# USB_Type_C.net
KiCad netlist of a schematic drawn in Altium Designer
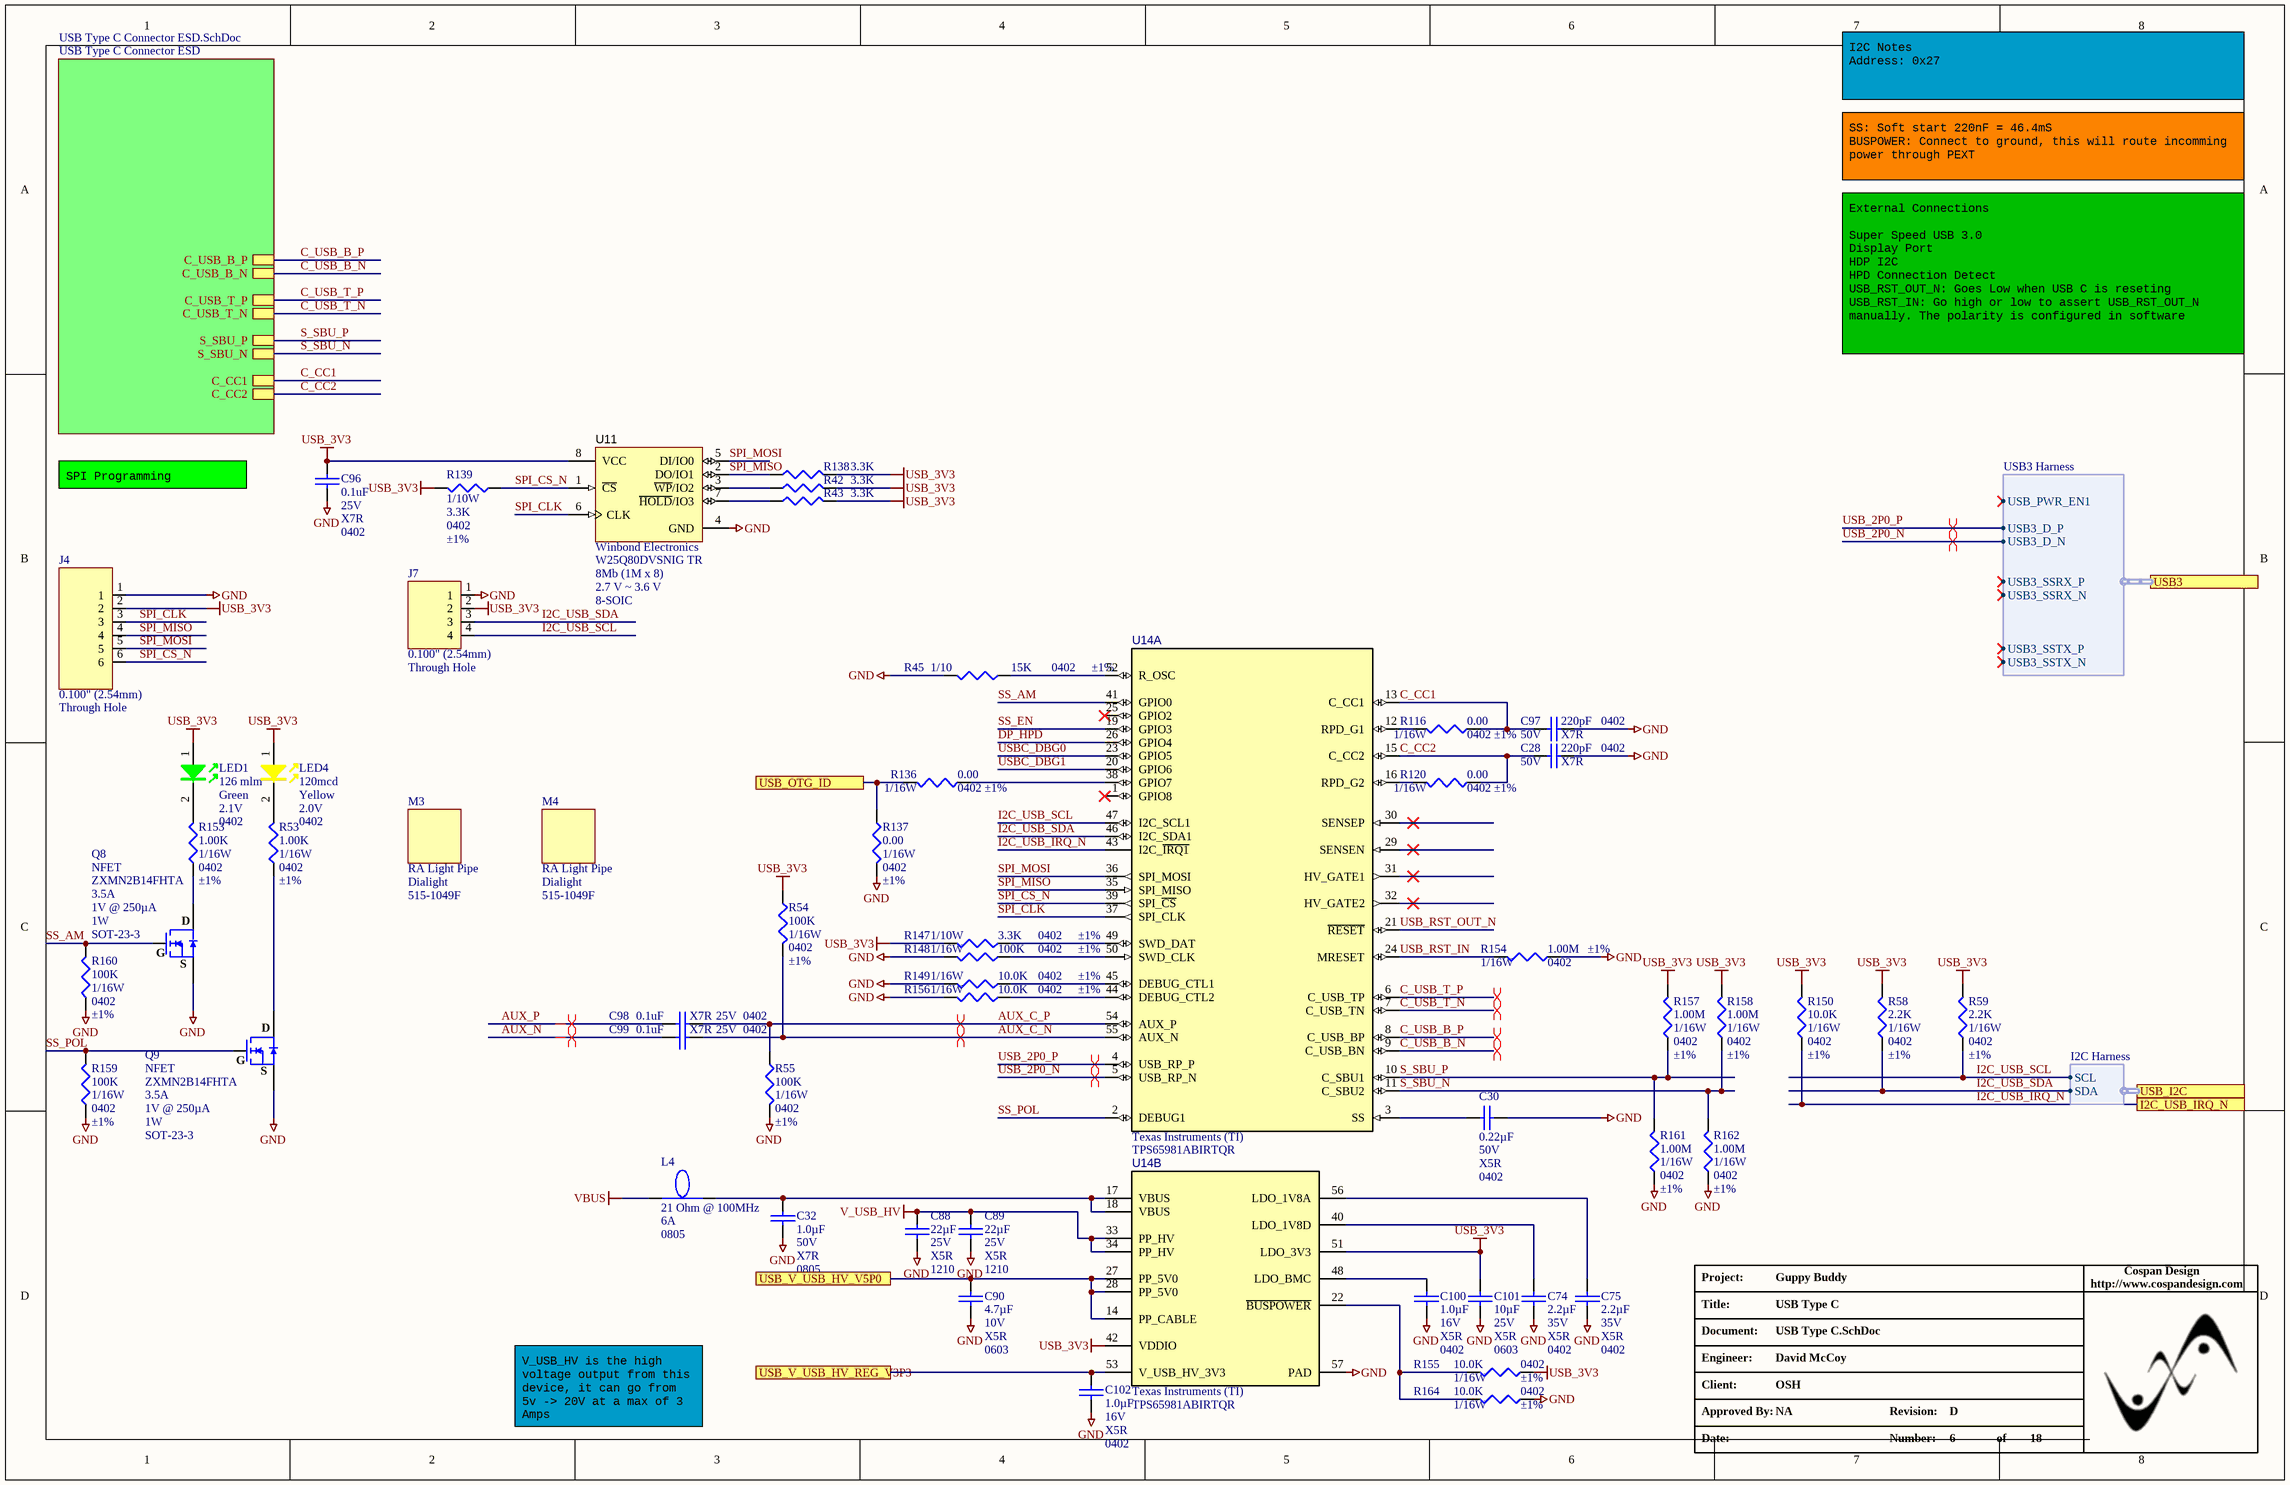
[diagram p0: USB Type C.SchDoc]

(export (version "E")
  (design (tool "Eeschema 10.0.6"))
  (components
    (comp (ref "C28")
      (value "220pF")
      (footprint "C_0402")
      (description "CAP CER 220PF 50V 10% X7R 0402")
      (fields
        (field (name "MANUFACTURER") "Murata Electronics North America")
        (field (name "MANUFACTURER PART NUMBER") "GRM155R71H221KA01D")
        (field (name "CAPACITANCE") "220pF")
        (field (name "VOLTAGE - RATED") "50V")
        (field (name "TEMPERATURE COEFFICIENT") "X7R")
        (field (name "PACKAGE / CASE") "0402")
      )
      (libsource (lib "Main Library") (part "C_0402_220PF_50V"))
    )
    (comp (ref "C30")
      (value "C_0402_0.22UF_50V")
      (footprint "C_0402")
      (description "CAP CER 0.22UF 50V X5R 0402")
      (fields
        (field (name "MANUFACTURER") "Taiyo Yuden")
        (field (name "MANUFACTURER PART NUMBER") "UMK105BJ224KV-F")
        (field (name "CAPACITANCE") "0.22µF")
        (field (name "VOLTAGE - RATED") "50V")
        (field (name "TEMPERATURE COEFFICIENT") "X5R")
        (field (name "PACKAGE / CASE") "0402")
      )
      (libsource (lib "Main Library") (part "C_0402_0.22UF_50V"))
    )
    (comp (ref "C32")
      (value "1.0uF")
      (footprint "C_ERA-0805")
      (description "CAP CER 1UF 50V X7R 0805")
      (fields
        (field (name "TOLERANCE") "10%")
        (field (name "CAPACITANCE") "1.0µF")
        (field (name "VOLTAGE - RATED") "50V")
        (field (name "TEMPERATURE COEFFICIENT") "X7R")
        (field (name "PACKAGE / CASE") "0805")
        (field (name "VOLTAGE") "50V")
      )
      (libsource (lib "Main LibraryX") (part "C_0805_1.0uF_50V"))
    )
    (comp (ref "C74")
      (value "C_0402_2.2uF_35V")
      (footprint "C_0402")
      (description "CAP CER 2.2UF 35V 20% X5R 0402")
      (fields
        (field (name "MANUFACTURER") "TDK Corporation")
        (field (name "MANUFACTURER PART NUMBER") "C1005X5R1V225K050BC")
        (field (name "CAPACITANCE") "2.2µF")
        (field (name "VOLTAGE - RATED") "35V")
        (field (name "TEMPERATURE COEFFICIENT") "X5R")
        (field (name "PACKAGE / CASE") "0402")
      )
      (libsource (lib "Main Library") (part "C_0402_2.2uF_35V"))
    )
    (comp (ref "C75")
      (value "C_0402_2.2uF_35V")
      (footprint "C_0402")
      (description "CAP CER 2.2UF 35V 20% X5R 0402")
      (fields
        (field (name "MANUFACTURER") "TDK Corporation")
        (field (name "MANUFACTURER PART NUMBER") "C1005X5R1V225K050BC")
        (field (name "CAPACITANCE") "2.2µF")
        (field (name "VOLTAGE - RATED") "35V")
        (field (name "TEMPERATURE COEFFICIENT") "X5R")
        (field (name "PACKAGE / CASE") "0402")
      )
      (libsource (lib "Main Library") (part "C_0402_2.2uF_35V"))
    )
    (comp (ref "C88")
      (value "22µF")
      (footprint "C_14-1210")
      (description "CAP CER 22UF 25V 20% X5R 1210")
      (fields
        (field (name "MANUFACTURER") "Taiyo Yuden")
        (field (name "MANUFACTURER PART NUMBER") "TMK325BJ226MM-T")
        (field (name "CAPACITANCE") "22µF")
        (field (name "VOLTAGE - RATED") "25V")
        (field (name "TEMPERATURE COEFFICIENT") "X5R")
        (field (name "PACKAGE / CASE") "1210")
      )
      (libsource (lib "Main Library") (part "C_1210_22µF"))
    )
    (comp (ref "C89")
      (value "22µF")
      (footprint "C_14-1210")
      (description "CAP CER 22UF 25V 20% X5R 1210")
      (fields
        (field (name "MANUFACTURER") "Taiyo Yuden")
        (field (name "MANUFACTURER PART NUMBER") "TMK325BJ226MM-T")
        (field (name "CAPACITANCE") "22µF")
        (field (name "VOLTAGE - RATED") "25V")
        (field (name "TEMPERATURE COEFFICIENT") "X5R")
        (field (name "PACKAGE / CASE") "1210")
      )
      (libsource (lib "Main Library") (part "C_1210_22µF"))
    )
    (comp (ref "C90")
      (value "4.7µF")
      (footprint "C_0603")
      (description "CAP CER 4.7UF 10V X5R 0603")
      (fields
        (field (name "TOLERANCE") "10%")
        (field (name "CAPACITANCE") "4.7µF")
        (field (name "VOLTAGE - RATED") "10V")
        (field (name "TEMPERATURE COEFFICIENT") "X5R")
        (field (name "PACKAGE / CASE") "0603")
        (field (name "VOLTAGE") "35V")
      )
      (libsource (lib "Main LibraryX") (part "C_0603_4.7uF_10V"))
    )
    (comp (ref "C96")
      (value "C_0402_0.1UF_25V")
      (footprint "C_0402")
      (description "CAP CER 0.1UF 25V X6S 0402")
      (fields
        (field (name "TOLERANCE") "10%")
        (field (name "CAPACITANCE") "0.1uF")
        (field (name "VOLTAGE - RATED") "25V")
        (field (name "TEMPERATURE COEFFICIENT") "X7R")
        (field (name "PACKAGE / CASE") "0402")
      )
      (libsource (lib "Cospan Design") (part "C_0402_0.1UF_25V"))
    )
    (comp (ref "C97")
      (value "220pF")
      (footprint "C_0402")
      (description "CAP CER 220PF 50V 10% X7R 0402")
      (fields
        (field (name "MANUFACTURER") "Murata Electronics North America")
        (field (name "MANUFACTURER PART NUMBER") "GRM155R71H221KA01D")
        (field (name "CAPACITANCE") "220pF")
        (field (name "VOLTAGE - RATED") "50V")
        (field (name "TEMPERATURE COEFFICIENT") "X7R")
        (field (name "PACKAGE / CASE") "0402")
      )
      (libsource (lib "Main Library") (part "C_0402_220PF_50V"))
    )
    (comp (ref "C98")
      (value "C_0402_0.1UF_25V")
      (footprint "C_0402")
      (description "CAP CER 0.1UF 25V X6S 0402")
      (fields
        (field (name "TOLERANCE") "10%")
        (field (name "CAPACITANCE") "0.1uF")
        (field (name "VOLTAGE - RATED") "25V")
        (field (name "TEMPERATURE COEFFICIENT") "X7R")
        (field (name "PACKAGE / CASE") "0402")
      )
      (libsource (lib "Cospan Design") (part "C_0402_0.1UF_25V"))
    )
    (comp (ref "C99")
      (value "C_0402_0.1UF_25V")
      (footprint "C_0402")
      (description "CAP CER 0.1UF 25V X6S 0402")
      (fields
        (field (name "TOLERANCE") "10%")
        (field (name "CAPACITANCE") "0.1uF")
        (field (name "VOLTAGE - RATED") "25V")
        (field (name "TEMPERATURE COEFFICIENT") "X7R")
        (field (name "PACKAGE / CASE") "0402")
      )
      (libsource (lib "Cospan Design") (part "C_0402_0.1UF_25V"))
    )
    (comp (ref "C100")
      (value "1.0uF")
      (footprint "C_0402")
      (description "CAP CER 1.0UF 16V X5R 0402")
      (fields
        (field (name "TOLERANCE") "10%")
        (field (name "CAPACITANCE") "1.0µF")
        (field (name "VOLTAGE - RATED") "16V")
        (field (name "TEMPERATURE COEFFICIENT") "X5R")
        (field (name "PACKAGE / CASE") "0402")
        (field (name "VOLTAGE") "16V")
      )
      (libsource (lib "Main LibraryX") (part "C_0402_1.0UF_16V"))
    )
    (comp (ref "C101")
      (value "C_0603_10µF")
      (footprint "C_ERA-0603")
      (description "CAP CER 10UF 16V X5R 0603")
      (fields
        (field (name "MANUFACTURER") "Murata Electronics North America")
        (field (name "MANUFACTURER PART NUMBER") "GRM188R61C106MA73D")
        (field (name "CAPACITANCE") "10µF")
        (field (name "VOLTAGE - RATED") "25V")
        (field (name "TEMPERATURE COEFFICIENT") "X5R")
        (field (name "PACKAGE / CASE") "0603")
      )
      (libsource (lib "Cospan Design") (part "C_0603_10µF"))
    )
    (comp (ref "C102")
      (value "1.0uF")
      (footprint "C_0402")
      (description "CAP CER 1.0UF 16V X5R 0402")
      (fields
        (field (name "TOLERANCE") "10%")
        (field (name "CAPACITANCE") "1.0µF")
        (field (name "VOLTAGE - RATED") "16V")
        (field (name "TEMPERATURE COEFFICIENT") "X5R")
        (field (name "PACKAGE / CASE") "0402")
        (field (name "VOLTAGE") "16V")
      )
      (libsource (lib "Main LibraryX") (part "C_0402_1.0UF_16V"))
    )
    (comp (ref "J4")
      (value "J_HDR1X6_THRHOLE_VERT")
      (footprint "HDR_1X6")
      (description "CONN HEADER .100\" 12POS TIN PCB")
      (fields
        (field (name "MANUFACTURER") "Samtec")
        (field (name "MANUFACTURER PART NUMBER") "TSW-106-07-T-S")
        (field (name "PITCH") "0.100\" (2.54mm)")
        (field (name "MOUNTING TYPE") "Through Hole")
      )
      (libsource (lib "Main Library") (part "J_HDR1X6_THRHOLE_VERT"))
    )
    (comp (ref "J7")
      (value "J_HDR1X4_THRHOLE_VERT")
      (footprint "HDR_1X4")
      (description "CONN HEADER .100\" 4POS TIN PCB")
      (fields
        (field (name "MANUFACTURER") "Samtec")
        (field (name "MANUFACTURER PART NUMBER") "TSW-104-07-T-S")
        (field (name "PITCH") "0.100\" (2.54mm)")
        (field (name "MOUNTING TYPE") "Through Hole")
      )
      (libsource (lib "Main Library") (part "J_HDR1X4_THRHOLE_VERT"))
    )
    (comp (ref "L4")
      (value "L_FB_21OHM_100MHZ")
      (footprint "C_ERA-0805")
      (description "FERRITE BEAD 21 OHM 0805 1LN")
      (fields
        (field (name "MANUFACTURER") "Taiyo Yuden")
        (field (name "MANUFACTURER PART NUMBER") "FBMJ2125HM210NT")
        (field (name "IMPEDANCE @ FREQUENCY") "21 Ohm @ 100MHz")
        (field (name "CURRENT RATING") "6A")
        (field (name "PACKAGE / CASE") "0805")
      )
      (libsource (lib "Main Library") (part "L_FB_21OHM_100MHZ"))
    )
    (comp (ref "LED1")
      (value "LED_GRN_0402")
      (footprint "DIOM1005X07L_GREEN")
      (description "LED 1X0.5MM 570NM GN WTR CLR SMD")
      (fields
        (field (name "MANUFACTURER") "Kingbright Corp")
        (field (name "MANUFACTURER PART NUMBER") "APHHS1005CGCK")
        (field (name "LUMINOUS FLUX @ CURRENT - TEST") "126 mlm")
        (field (name "COLOR") "Green")
        (field (name "VOLTAGE - FORWARD (VF) TYP") "2.1V")
        (field (name "PACKAGE / CASE") "0402")
      )
      (libsource (lib "Main Library") (part "LED_GRN_0402"))
    )
    (comp (ref "LED4")
      (value "LED_YLW_0402")
      (footprint "DIOM1005X07L_YELLOW")
      (description "LED 1X0.5MM 590NM YW WTR CLR SMD")
      (fields
        (field (name "MANUFACTURER") "Kingbright Corp")
        (field (name "MANUFACTURER PART NUMBER") "APHHS1005SYCK")
        (field (name "MILLICANDELA RATING") "120mcd")
        (field (name "COLOR") "Yellow")
        (field (name "VOLTAGE - FORWARD (VF) TYP") "2.0V")
        (field (name "PACKAGE / CASE") "0402")
      )
      (libsource (lib "Main Library") (part "LED_YLW_0402"))
    )
    (comp (ref "M3")
      (value "RA Light Pipe")
      (footprint "RA_LIGHTPIPE")
      (description "OPTICAL LIGHT PIPE")
      (fields
        (field (name "MANUFACTURER 1") "Dialight")
        (field (name "MANUFACTURER PART NUMBER 1") "515-1049F")
      )
      (libsource (lib "Cospan Design") (part "M_RA_LIGHTPIPE_7513D2-S"))
    )
    (comp (ref "M4")
      (value "RA Light Pipe")
      (footprint "RA_LIGHTPIPE")
      (description "OPTICAL LIGHT PIPE")
      (fields
        (field (name "MANUFACTURER 1") "Dialight")
        (field (name "MANUFACTURER PART NUMBER 1") "515-1049F")
      )
      (libsource (lib "Cospan Design") (part "M_RA_LIGHTPIPE_7513D2-S"))
    )
    (comp (ref "Q8")
      (value "NFET")
      (footprint "SOT-23A")
      (description "MOSFET N-CH 20V 3.5A SOT23-3")
      (fields
        (field (name "MANUFACTURER") "Diodes Incorporated")
        (field (name "MANUFACTURER PART NUMBER") "ZXMN2B14FHTA")
        (field (name "CURRENT - CONTINUOUS DRAIN (ID) @ 25° C") "3.5A")
        (field (name "VGS(TH) (MAX) @ ID") "1V @ 250µA")
        (field (name "POWER - MAX") "1W")
        (field (name "PACKAGE / CASE") "SOT-23-3")
      )
      (libsource (lib "Main LibraryX") (part "Q_NFET_3.50A_SOT23"))
    )
    (comp (ref "Q9")
      (value "NFET")
      (footprint "SOT-23A")
      (description "MOSFET N-CH 20V 3.5A SOT23-3")
      (fields
        (field (name "MANUFACTURER") "Diodes Incorporated")
        (field (name "MANUFACTURER PART NUMBER") "ZXMN2B14FHTA")
        (field (name "CURRENT - CONTINUOUS DRAIN (ID) @ 25° C") "3.5A")
        (field (name "VGS(TH) (MAX) @ ID") "1V @ 250µA")
        (field (name "POWER - MAX") "1W")
        (field (name "PACKAGE / CASE") "SOT-23-3")
      )
      (libsource (lib "Main LibraryX") (part "Q_NFET_3.50A_SOT23"))
    )
    (comp (ref "R42")
      (value "3.3k Ohms")
      (footprint "R_0402")
      (description "RES 3.30K OHM 1/10W 1% 0402 SM")
      (fields
        (field (name "MANUFACTURER") "Panasonic - ECG")
        (field (name "MANUFACTURER PART NUMBER") "ERJ-2RKF3301X")
        (field (name "RESISTANCE IN OHMS") "3.3K")
      )
      (libsource (lib "Main Library") (part "R_0402_3.3K"))
    )
    (comp (ref "R43")
      (value "3.3k Ohms")
      (footprint "R_0402")
      (description "RES 3.30K OHM 1/10W 1% 0402 SM")
      (fields
        (field (name "MANUFACTURER") "Panasonic - ECG")
        (field (name "MANUFACTURER PART NUMBER") "ERJ-2RKF3301X")
        (field (name "RESISTANCE IN OHMS") "3.3K")
      )
      (libsource (lib "Main Library") (part "R_0402_3.3K"))
    )
    (comp (ref "R45")
      (value "R_0402_15.0K")
      (footprint "R_0402")
      (description "RES 15.0K OHM 1/10W 1% 0402 SMD")
      (fields
        (field (name "MANUFACTURER") "Panasonic - ECG")
        (field (name "MANUFACTURER PART NUMBER") "ERJ-2RKF1502X")
        (field (name "RESISTANCE IN OHMS") "15K")
        (field (name "POWER (WATTS)") "1/10")
        (field (name "CASE") "0402")
        (field (name "TOLERANCE") "±1%")
      )
      (libsource (lib "Main Library") (part "R_0402_15.0K"))
    )
    (comp (ref "R53")
      (value "1.0k Ohms")
      (footprint "R_0402")
      (description "RES 1.00K OHM 1/16W 1% 0402 SMD")
      (fields
        (field (name "MANUFACTURER") "Yageo")
        (field (name "MANUFACTURER PART NUMBER") "RC0402FR-071KL")
        (field (name "RESISTANCE IN OHMS") "1.00K")
        (field (name "POWER (WATTS)") "1/16W")
        (field (name "CASE") "0402")
        (field (name "TOLERANCE") "±1%")
      )
      (libsource (lib "Main Library") (part "R_0402_1.0K"))
    )
    (comp (ref "R54")
      (value "R_0402_100K")
      (footprint "R_0402")
      (description "RES SMD 100K OHM 1% 1/16W 0402")
      (fields
        (field (name "MANUFACTURER") "Yageo")
        (field (name "MANUFACTURER PART NUMBER") "RC0402FR-07100KL")
        (field (name "RESISTANCE IN OHMS") "100K")
        (field (name "POWER (WATTS)") "1/16W")
        (field (name "CASE") "0402")
        (field (name "TOLERANCE") "±1%")
      )
      (libsource (lib "Cospan Design") (part "R_0402_100K"))
    )
    (comp (ref "R55")
      (value "R_0402_100K")
      (footprint "R_0402")
      (description "RES SMD 100K OHM 1% 1/16W 0402")
      (fields
        (field (name "MANUFACTURER") "Yageo")
        (field (name "MANUFACTURER PART NUMBER") "RC0402FR-07100KL")
        (field (name "RESISTANCE IN OHMS") "100K")
        (field (name "POWER (WATTS)") "1/16W")
        (field (name "CASE") "0402")
        (field (name "TOLERANCE") "±1%")
      )
      (libsource (lib "Cospan Design") (part "R_0402_100K"))
    )
    (comp (ref "R58")
      (value "R_0402_2.2K")
      (footprint "R_0402")
      (description "RES SMD 2.2K OHM 1% 1/10W 0402")
      (fields
        (field (name "MANUFACTURER") "Panasonic Electronic Components")
        (field (name "MANUFACTURER PART NUMBER") "ERJ-2RKF2201X")
        (field (name "RESISTANCE IN OHMS") "2.2K")
        (field (name "POWER (WATTS)") "1/16W")
        (field (name "CASE") "0402")
        (field (name "TOLERANCE") "±1%")
      )
      (libsource (lib "Cospan Design") (part "R_0402_2.2K"))
    )
    (comp (ref "R59")
      (value "R_0402_2.2K")
      (footprint "R_0402")
      (description "RES SMD 2.2K OHM 1% 1/10W 0402")
      (fields
        (field (name "MANUFACTURER") "Panasonic Electronic Components")
        (field (name "MANUFACTURER PART NUMBER") "ERJ-2RKF2201X")
        (field (name "RESISTANCE IN OHMS") "2.2K")
        (field (name "POWER (WATTS)") "1/16W")
        (field (name "CASE") "0402")
        (field (name "TOLERANCE") "±1%")
      )
      (libsource (lib "Cospan Design") (part "R_0402_2.2K"))
    )
    (comp (ref "R116")
      (value "0.0 Ohms")
      (footprint "R_0402")
      (description "RES 0.00 OHM 1/16W 1% 0402 SMD")
      (fields
        (field (name "MANUFACTURER") "Yageo")
        (field (name "MANUFACTURER PART NUMBER") "RC0402JR-070RL")
        (field (name "RESISTANCE IN OHMS") "0.00")
        (field (name "POWER (WATTS)") "1/16W")
        (field (name "CASE") "0402")
        (field (name "TOLERANCE") "±1%")
      )
      (libsource (lib "Cospan Design") (part "R_0402_0.00"))
    )
    (comp (ref "R120")
      (value "0.0 Ohms")
      (footprint "R_0402")
      (description "RES 0.00 OHM 1/16W 1% 0402 SMD")
      (fields
        (field (name "MANUFACTURER") "Yageo")
        (field (name "MANUFACTURER PART NUMBER") "RC0402JR-070RL")
        (field (name "RESISTANCE IN OHMS") "0.00")
        (field (name "POWER (WATTS)") "1/16W")
        (field (name "CASE") "0402")
        (field (name "TOLERANCE") "±1%")
      )
      (libsource (lib "Cospan Design") (part "R_0402_0.00"))
    )
    (comp (ref "R136")
      (value "0.0 Ohms")
      (footprint "R_0402")
      (description "RES 0.00 OHM 1/16W 1% 0402 SMD")
      (fields
        (field (name "MANUFACTURER") "Yageo")
        (field (name "MANUFACTURER PART NUMBER") "RC0402JR-070RL")
        (field (name "RESISTANCE IN OHMS") "0.00")
        (field (name "POWER (WATTS)") "1/16W")
        (field (name "CASE") "0402")
        (field (name "TOLERANCE") "±1%")
      )
      (libsource (lib "Cospan Design") (part "R_0402_0.00"))
    )
    (comp (ref "R137")
      (value "0.0 Ohms")
      (footprint "R_0402")
      (description "RES 0.00 OHM 1/16W 1% 0402 SMD")
      (fields
        (field (name "MANUFACTURER") "Yageo")
        (field (name "MANUFACTURER PART NUMBER") "RC0402JR-070RL")
        (field (name "RESISTANCE IN OHMS") "0.00")
        (field (name "POWER (WATTS)") "1/16W")
        (field (name "CASE") "0402")
        (field (name "TOLERANCE") "±1%")
      )
      (libsource (lib "Cospan Design") (part "R_0402_0.00"))
    )
    (comp (ref "R138")
      (value "3.3k Ohms")
      (footprint "R_0402")
      (description "RES 3.30K OHM 1/10W 1% 0402 SM")
      (fields
        (field (name "MANUFACTURER") "Panasonic - ECG")
        (field (name "MANUFACTURER PART NUMBER") "ERJ-2RKF3301X")
        (field (name "RESISTANCE IN OHMS") "3.3K")
      )
      (libsource (lib "Main Library") (part "R_0402_3.3K"))
    )
    (comp (ref "R139")
      (value "3.3k Ohms")
      (footprint "R_0402")
      (description "RES 3.30K OHM 1/10W 1% 0402 SM")
      (fields
        (field (name "MANUFACTURER") "Panasonic - ECG")
        (field (name "MANUFACTURER PART NUMBER") "ERJ-2RKF3301X")
        (field (name "POWER (WATTS)") "1/10W")
        (field (name "RESISTANCE IN OHMS") "3.3K")
        (field (name "CASE") "0402")
        (field (name "TOLERANCE") "±1%")
      )
      (libsource (lib "Main Library") (part "R_0402_3.3K"))
    )
    (comp (ref "R147")
      (value "3.3k Ohms")
      (footprint "R_0402")
      (description "RES 3.30K OHM 1/10W 1% 0402 SM")
      (fields
        (field (name "MANUFACTURER") "Panasonic - ECG")
        (field (name "MANUFACTURER PART NUMBER") "ERJ-2RKF3301X")
        (field (name "POWER (WATTS)") "1/10W")
        (field (name "RESISTANCE IN OHMS") "3.3K")
        (field (name "CASE") "0402")
        (field (name "TOLERANCE") "±1%")
      )
      (libsource (lib "Main Library") (part "R_0402_3.3K"))
    )
    (comp (ref "R148")
      (value "R_0402_100K")
      (footprint "R_0402")
      (description "RES SMD 100K OHM 1% 1/16W 0402")
      (fields
        (field (name "MANUFACTURER") "Yageo")
        (field (name "MANUFACTURER PART NUMBER") "RC0402FR-07100KL")
        (field (name "RESISTANCE IN OHMS") "100K")
        (field (name "POWER (WATTS)") "1/16W")
        (field (name "CASE") "0402")
        (field (name "TOLERANCE") "±1%")
      )
      (libsource (lib "Cospan Design") (part "R_0402_100K"))
    )
    (comp (ref "R149")
      (value "R_0402_10.0K")
      (footprint "R_0402")
      (description "RES 10.0K OHM 1/16W 1% 0402 SMD")
      (fields
        (field (name "MANUFACTURER") "Stackpole Electronics Inc")
        (field (name "MANUFACTURER PART NUMBER") "RMCF0402FT10K0")
        (field (name "RESISTANCE IN OHMS") "10.0K")
        (field (name "POWER (WATTS)") "1/16W")
        (field (name "CASE") "0402")
        (field (name "TOLERANCE") "±1%")
      )
      (libsource (lib "Cospan Design") (part "R_0402_10.0K"))
    )
    (comp (ref "R150")
      (value "R_0402_10.0K")
      (footprint "R_0402")
      (description "RES 10.0K OHM 1/16W 1% 0402 SMD")
      (fields
        (field (name "MANUFACTURER") "Stackpole Electronics Inc")
        (field (name "MANUFACTURER PART NUMBER") "RMCF0402FT10K0")
        (field (name "RESISTANCE IN OHMS") "10.0K")
        (field (name "POWER (WATTS)") "1/16W")
        (field (name "CASE") "0402")
        (field (name "TOLERANCE") "±1%")
      )
      (libsource (lib "Cospan Design") (part "R_0402_10.0K"))
    )
    (comp (ref "R153")
      (value "1.0k Ohms")
      (footprint "R_0402")
      (description "RES 1.00K OHM 1/16W 1% 0402 SMD")
      (fields
        (field (name "MANUFACTURER") "Yageo")
        (field (name "MANUFACTURER PART NUMBER") "RC0402FR-071KL")
        (field (name "RESISTANCE IN OHMS") "1.00K")
        (field (name "POWER (WATTS)") "1/16W")
        (field (name "CASE") "0402")
        (field (name "TOLERANCE") "±1%")
      )
      (libsource (lib "Main Library") (part "R_0402_1.0K"))
    )
    (comp (ref "R154")
      (value "1.0M Ohms")
      (footprint "R_0402")
      (description "RES 1.00M OHM 1/16W 1% 0402 SMD")
      (fields
        (field (name "MANUFACTURER") "Vishay/Dale")
        (field (name "MANUFACTURER PART NUMBER") "CRCW04021M00FKED")
        (field (name "RESISTANCE IN OHMS") "1.00M")
        (field (name "POWER (WATTS)") "1/16W")
        (field (name "CASE") "0402")
        (field (name "TOLERANCE") "±1%")
      )
      (libsource (lib "Main Library") (part "R_0402_1.0M"))
    )
    (comp (ref "R155")
      (value "R_0402_10.0K")
      (footprint "R_0402")
      (description "RES 10.0K OHM 1/16W 1% 0402 SMD")
      (fields
        (field (name "MANUFACTURER") "Stackpole Electronics Inc")
        (field (name "MANUFACTURER PART NUMBER") "RMCF0402FT10K0")
        (field (name "RESISTANCE IN OHMS") "10.0K")
        (field (name "POWER (WATTS)") "1/16W")
        (field (name "CASE") "0402")
        (field (name "TOLERANCE") "±1%")
      )
      (libsource (lib "Cospan Design") (part "R_0402_10.0K"))
    )
    (comp (ref "R156")
      (value "R_0402_10.0K")
      (footprint "R_0402")
      (description "RES 10.0K OHM 1/16W 1% 0402 SMD")
      (fields
        (field (name "MANUFACTURER") "Stackpole Electronics Inc")
        (field (name "MANUFACTURER PART NUMBER") "RMCF0402FT10K0")
        (field (name "RESISTANCE IN OHMS") "10.0K")
        (field (name "POWER (WATTS)") "1/16W")
        (field (name "CASE") "0402")
        (field (name "TOLERANCE") "±1%")
      )
      (libsource (lib "Cospan Design") (part "R_0402_10.0K"))
    )
    (comp (ref "R157")
      (value "1.0M Ohms")
      (footprint "R_0402")
      (description "RES 1.00M OHM 1/16W 1% 0402 SMD")
      (fields
        (field (name "MANUFACTURER") "Vishay/Dale")
        (field (name "MANUFACTURER PART NUMBER") "CRCW04021M00FKED")
        (field (name "RESISTANCE IN OHMS") "1.00M")
        (field (name "POWER (WATTS)") "1/16W")
        (field (name "CASE") "0402")
        (field (name "TOLERANCE") "±1%")
      )
      (libsource (lib "Main Library") (part "R_0402_1.0M"))
    )
    (comp (ref "R158")
      (value "1.0M Ohms")
      (footprint "R_0402")
      (description "RES 1.00M OHM 1/16W 1% 0402 SMD")
      (fields
        (field (name "MANUFACTURER") "Vishay/Dale")
        (field (name "MANUFACTURER PART NUMBER") "CRCW04021M00FKED")
        (field (name "RESISTANCE IN OHMS") "1.00M")
        (field (name "POWER (WATTS)") "1/16W")
        (field (name "CASE") "0402")
        (field (name "TOLERANCE") "±1%")
      )
      (libsource (lib "Main Library") (part "R_0402_1.0M"))
    )
    (comp (ref "R159")
      (value "R_0402_100.0K")
      (footprint "R_0402")
      (description "RES 100K OHM 1/16W 1% 0402 SMD")
      (fields
        (field (name "MANUFACTURER") "Stackpole Electronics Inc")
        (field (name "MANUFACTURER PART NUMBER") "RMCF0402FT100K")
        (field (name "RESISTANCE IN OHMS") "100K")
        (field (name "POWER (WATTS)") "1/16W")
        (field (name "CASE") "0402")
        (field (name "TOLERANCE") "±1%")
      )
      (libsource (lib "Main Library") (part "R_0402_100.0K"))
    )
    (comp (ref "R160")
      (value "R_0402_100.0K")
      (footprint "R_0402")
      (description "RES 100K OHM 1/16W 1% 0402 SMD")
      (fields
        (field (name "MANUFACTURER") "Stackpole Electronics Inc")
        (field (name "MANUFACTURER PART NUMBER") "RMCF0402FT100K")
        (field (name "RESISTANCE IN OHMS") "100K")
        (field (name "POWER (WATTS)") "1/16W")
        (field (name "CASE") "0402")
        (field (name "TOLERANCE") "±1%")
      )
      (libsource (lib "Main Library") (part "R_0402_100.0K"))
    )
    (comp (ref "R161")
      (value "1.0M Ohms")
      (footprint "R_0402")
      (description "RES 1.00M OHM 1/16W 1% 0402 SMD")
      (fields
        (field (name "MANUFACTURER") "Vishay/Dale")
        (field (name "MANUFACTURER PART NUMBER") "CRCW04021M00FKED")
        (field (name "RESISTANCE IN OHMS") "1.00M")
        (field (name "POWER (WATTS)") "1/16W")
        (field (name "CASE") "0402")
        (field (name "TOLERANCE") "±1%")
      )
      (libsource (lib "Main Library") (part "R_0402_1.0M"))
    )
    (comp (ref "R162")
      (value "1.0M Ohms")
      (footprint "R_0402")
      (description "RES 1.00M OHM 1/16W 1% 0402 SMD")
      (fields
        (field (name "MANUFACTURER") "Vishay/Dale")
        (field (name "MANUFACTURER PART NUMBER") "CRCW04021M00FKED")
        (field (name "RESISTANCE IN OHMS") "1.00M")
        (field (name "POWER (WATTS)") "1/16W")
        (field (name "CASE") "0402")
        (field (name "TOLERANCE") "±1%")
      )
      (libsource (lib "Main Library") (part "R_0402_1.0M"))
    )
    (comp (ref "R164")
      (value "R_0402_10.0K")
      (footprint "R_0402")
      (description "RES 10.0K OHM 1/16W 1% 0402 SMD")
      (fields
        (field (name "MANUFACTURER") "Stackpole Electronics Inc")
        (field (name "MANUFACTURER PART NUMBER") "RMCF0402FT10K0")
        (field (name "RESISTANCE IN OHMS") "10.0K")
        (field (name "POWER (WATTS)") "1/16W")
        (field (name "CASE") "0402")
        (field (name "TOLERANCE") "±1%")
      )
      (libsource (lib "Cospan Design") (part "R_0402_10.0K"))
    )
    (comp (ref "U11")
      (value "U_W25Q80DVSNIG")
      (footprint "SOIC-8 - TI")
      (description "3V, 8Mbit, Serial Flash Memory with Dual and Qual SPI, SOIC-8")
      (fields
        (field (name "MANUFACTURER") "Winbond Electronics")
        (field (name "MANUFACTURER PART NUMBER") "W25Q80DVSNIG TR")
        (field (name "MEMORY SIZE") "8Mb (1M x 8)")
        (field (name "VOLTAGE - SUPPLY") "2.7 V ~ 3.6 V")
        (field (name "SUPPLIER DEVICE PACKAGE") "8-SOIC")
      )
      (libsource (lib "Cospan Design") (part "U_W25Q80DVSNIG"))
    )
    (comp (ref "U14")
      (value "~")
      (footprint "RWE0056B")
      (description "USB, Type-C Controller PMIC 56-QFN (8x8)")
      (fields
        (field (name "MANUFACTURER") "Texas Instruments (TI)")
        (field (name "MANUFACTURER PART NUMBER") "TPS65981ABIRTQR")
      )
      (libsource (lib "Cospan Design") (part "U_TPS65981ABQWRWERQ1"))
    )
  )
  (nets
    (net (code "4") (name "/AUX_C_N") (class "Default")
      (node (ref "C99") (pin "1") (pinfunction "1_1") (pintype "passive"))
      (node (ref "R54") (pin "1") (pinfunction "1_1") (pintype "passive"))
      (node (ref "U14") (pin "55") (pinfunction "AUX_N_55") (pintype "bidirectional"))
    )
    (net (code "5") (name "/AUX_C_P") (class "Default")
      (node (ref "C98") (pin "1") (pinfunction "1_1") (pintype "passive"))
      (node (ref "R55") (pin "2") (pinfunction "2_2") (pintype "passive"))
      (node (ref "U14") (pin "54") (pinfunction "AUX_P_54") (pintype "bidirectional"))
    )
    (net (code "6") (name "/AUX_N") (class "Default")
      (node (ref "C99") (pin "2") (pinfunction "2_2") (pintype "passive"))
    )
    (net (code "7") (name "/AUX_P") (class "Default")
      (node (ref "C98") (pin "2") (pinfunction "2_2") (pintype "passive"))
    )
    (net (code "8") (name "/C_CC1") (class "Default")
      (node (ref "C97") (pin "2") (pinfunction "2_2") (pintype "passive"))
      (node (ref "R116") (pin "2") (pinfunction "2_2") (pintype "passive"))
      (node (ref "U14") (pin "13") (pinfunction "C_CC1_13") (pintype "bidirectional"))
    )
    (net (code "9") (name "/C_CC2") (class "Default")
      (node (ref "C28") (pin "2") (pinfunction "2_2") (pintype "passive"))
      (node (ref "R120") (pin "2") (pinfunction "2_2") (pintype "passive"))
      (node (ref "U14") (pin "15") (pinfunction "C_CC2_15") (pintype "bidirectional"))
    )
    (net (code "10") (name "/C_USB_B_N") (class "Default")
      (node (ref "U14") (pin "9") (pinfunction "C_USB_BN_9") (pintype "bidirectional"))
    )
    (net (code "11") (name "/C_USB_B_P") (class "Default")
      (node (ref "U14") (pin "8") (pinfunction "C_USB_BP_8") (pintype "bidirectional"))
    )
    (net (code "12") (name "/C_USB_T_N") (class "Default")
      (node (ref "U14") (pin "7") (pinfunction "C_USB_TN_7") (pintype "bidirectional"))
    )
    (net (code "13") (name "/C_USB_T_P") (class "Default")
      (node (ref "U14") (pin "6") (pinfunction "C_USB_TP_6") (pintype "bidirectional"))
    )
    (net (code "14") (name "/DP_HPD") (class "Default")
      (node (ref "U14") (pin "26") (pinfunction "GPIO4_26") (pintype "bidirectional"))
    )
    (net (code "15") (name "/I2C_USB_IRQ_N") (class "Default")
      (node (ref "R150") (pin "2") (pinfunction "2_2") (pintype "passive"))
      (node (ref "U14") (pin "43") (pinfunction "I2C_~{IRQ1}_43") (pintype "open_collector"))
    )
    (net (code "16") (name "/I2C_USB_SCL") (class "Default")
      (node (ref "J7") (pin "4") (pinfunction "4_4") (pintype "passive"))
      (node (ref "R59") (pin "2") (pinfunction "2_2") (pintype "passive"))
      (node (ref "U14") (pin "47") (pinfunction "I2C_SCL1_47") (pintype "bidirectional"))
    )
    (net (code "17") (name "/I2C_USB_SDA") (class "Default")
      (node (ref "J7") (pin "3") (pinfunction "3_3") (pintype "passive"))
      (node (ref "R58") (pin "2") (pinfunction "2_2") (pintype "passive"))
      (node (ref "U14") (pin "46") (pinfunction "I2C_SDA1_46") (pintype "bidirectional"))
    )
    (net (code "18") (name "/SPI_CLK") (class "Default")
      (node (ref "J4") (pin "3") (pinfunction "3_3") (pintype "passive"))
      (node (ref "U11") (pin "6") (pinfunction "CLK_6") (pintype "input"))
      (node (ref "U14") (pin "37") (pinfunction "SPI_CLK_37") (pintype "output"))
    )
    (net (code "19") (name "/SPI_CS_N") (class "Default")
      (node (ref "J4") (pin "6") (pinfunction "6_6") (pintype "passive"))
      (node (ref "R139") (pin "2") (pinfunction "2_2") (pintype "passive"))
      (node (ref "U11") (pin "1") (pinfunction "CS_1") (pintype "input"))
      (node (ref "U14") (pin "39") (pinfunction "SPI_~{CS}_39") (pintype "output"))
    )
    (net (code "20") (name "/SPI_MISO") (class "Default")
      (node (ref "J4") (pin "4") (pinfunction "4_4") (pintype "passive"))
      (node (ref "R138") (pin "2") (pinfunction "2_2") (pintype "passive"))
      (node (ref "U11") (pin "2") (pinfunction "DO/IO1_2") (pintype "bidirectional"))
      (node (ref "U14") (pin "35") (pinfunction "SPI_MISO_35") (pintype "input"))
    )
    (net (code "21") (name "/SPI_MOSI") (class "Default")
      (node (ref "J4") (pin "5") (pinfunction "5_5") (pintype "passive"))
      (node (ref "U11") (pin "5") (pinfunction "DI/IO0_5") (pintype "bidirectional"))
      (node (ref "U14") (pin "36") (pinfunction "SPI_MOSI_36") (pintype "output"))
    )
    (net (code "22") (name "/SS_AM") (class "Default")
      (node (ref "Q8") (pin "1") (pinfunction "G_1") (pintype "passive"))
      (node (ref "R160") (pin "1") (pinfunction "1_1") (pintype "passive"))
      (node (ref "U14") (pin "41") (pinfunction "GPIO0_41") (pintype "bidirectional"))
    )
    (net (code "23") (name "/SS_EN") (class "Default")
      (node (ref "U14") (pin "19") (pinfunction "GPIO3_19") (pintype "bidirectional"))
    )
    (net (code "24") (name "/SS_POL") (class "Default")
      (node (ref "Q9") (pin "1") (pinfunction "G_1") (pintype "passive"))
      (node (ref "R159") (pin "1") (pinfunction "1_1") (pintype "passive"))
      (node (ref "U14") (pin "2") (pinfunction "DEBUG1_2") (pintype "bidirectional"))
    )
    (net (code "25") (name "/S_SBU_N") (class "Default")
      (node (ref "R158") (pin "2") (pinfunction "2_2") (pintype "passive"))
      (node (ref "R162") (pin "1") (pinfunction "1_1") (pintype "passive"))
      (node (ref "U14") (pin "11") (pinfunction "C_SBU2_11") (pintype "bidirectional"))
    )
    (net (code "26") (name "/S_SBU_P") (class "Default")
      (node (ref "R157") (pin "2") (pinfunction "2_2") (pintype "passive"))
      (node (ref "R161") (pin "1") (pinfunction "1_1") (pintype "passive"))
      (node (ref "U14") (pin "10") (pinfunction "C_SBU1_10") (pintype "bidirectional"))
    )
    (net (code "27") (name "/USBC_DBG0") (class "Default")
      (node (ref "U14") (pin "23") (pinfunction "GPIO5_23") (pintype "bidirectional"))
    )
    (net (code "28") (name "/USBC_DBG1") (class "Default")
      (node (ref "U14") (pin "20") (pinfunction "GPIO6_20") (pintype "bidirectional"))
    )
    (net (code "29") (name "/USB_2P0_N") (class "Default")
      (node (ref "U14") (pin "5") (pinfunction "USB_RP_N_5") (pintype "bidirectional"))
    )
    (net (code "30") (name "/USB_2P0_P") (class "Default")
      (node (ref "U14") (pin "4") (pinfunction "USB_RP_P_4") (pintype "bidirectional"))
    )
    (net (code "31") (name "/USB_OTG_ID") (class "Default")
      (node (ref "R136") (pin "1") (pinfunction "1_1") (pintype "passive"))
      (node (ref "R137") (pin "2") (pinfunction "2_2") (pintype "passive"))
    )
    (net (code "32") (name "/USB_RST_IN") (class "Default")
      (node (ref "R154") (pin "1") (pinfunction "1_1") (pintype "passive"))
      (node (ref "U14") (pin "24") (pinfunction "MRESET_24") (pintype "bidirectional"))
    )
    (net (code "33") (name "/USB_RST_OUT_N") (class "Default")
      (node (ref "U14") (pin "21") (pinfunction "RESET_21") (pintype "bidirectional"))
    )
    (net (code "34") (name "/USB_V_USB_HV_REG_V3P3") (class "Default")
      (node (ref "C102") (pin "2") (pinfunction "2_2") (pintype "passive"))
      (node (ref "U14") (pin "53") (pinfunction "VIN_3V3_53") (pintype "power_in"))
    )
    (net (code "35") (name "/USB_V_USB_HV_V5P0") (class "Default")
      (node (ref "C90") (pin "2") (pinfunction "2_2") (pintype "passive"))
      (node (ref "U14") (pin "14") (pinfunction "PP_CABLE_14") (pintype "power_in"))
      (node (ref "U14") (pin "27") (pinfunction "PP_5V0_27") (pintype "power_in"))
      (node (ref "U14") (pin "28") (pinfunction "PP_5V0_28") (pintype "power_in"))
    )
    (net (code "38") (name "GND") (class "Default")
      (node (ref "C100") (pin "1") (pinfunction "1_1") (pintype "passive"))
      (node (ref "C101") (pin "1") (pinfunction "1_1") (pintype "passive"))
      (node (ref "C102") (pin "1") (pinfunction "1_1") (pintype "passive"))
      (node (ref "C28") (pin "1") (pinfunction "1_1") (pintype "passive"))
      (node (ref "C30") (pin "1") (pinfunction "1_1") (pintype "passive"))
      (node (ref "C32") (pin "1") (pinfunction "1_1") (pintype "passive"))
      (node (ref "C74") (pin "1") (pinfunction "1_1") (pintype "passive"))
      (node (ref "C75") (pin "1") (pinfunction "1_1") (pintype "passive"))
      (node (ref "C88") (pin "1") (pinfunction "1_1") (pintype "passive"))
      (node (ref "C89") (pin "1") (pinfunction "1_1") (pintype "passive"))
      (node (ref "C90") (pin "1") (pinfunction "1_1") (pintype "passive"))
      (node (ref "C96") (pin "1") (pinfunction "1_1") (pintype "passive"))
      (node (ref "C97") (pin "1") (pinfunction "1_1") (pintype "passive"))
      (node (ref "J4") (pin "1") (pinfunction "1_1") (pintype "passive"))
      (node (ref "J7") (pin "1") (pinfunction "1_1") (pintype "passive"))
      (node (ref "Q8") (pin "2") (pinfunction "S_2") (pintype "passive"))
      (node (ref "Q9") (pin "2") (pinfunction "S_2") (pintype "passive"))
      (node (ref "R137") (pin "1") (pinfunction "1_1") (pintype "passive"))
      (node (ref "R148") (pin "1") (pinfunction "1_1") (pintype "passive"))
      (node (ref "R149") (pin "1") (pinfunction "1_1") (pintype "passive"))
      (node (ref "R154") (pin "2") (pinfunction "2_2") (pintype "passive"))
      (node (ref "R156") (pin "1") (pinfunction "1_1") (pintype "passive"))
      (node (ref "R159") (pin "2") (pinfunction "2_2") (pintype "passive"))
      (node (ref "R160") (pin "2") (pinfunction "2_2") (pintype "passive"))
      (node (ref "R161") (pin "2") (pinfunction "2_2") (pintype "passive"))
      (node (ref "R162") (pin "2") (pinfunction "2_2") (pintype "passive"))
      (node (ref "R164") (pin "2") (pinfunction "2_2") (pintype "passive"))
      (node (ref "R45") (pin "1") (pinfunction "1_1") (pintype "passive"))
      (node (ref "R55") (pin "1") (pinfunction "1_1") (pintype "passive"))
      (node (ref "U11") (pin "4") (pinfunction "GND_4") (pintype "power_in"))
      (node (ref "U14") (pin "57") (pinfunction "PAD_57") (pintype "power_in"))
    )
    (net (code "39") (name "Net-(C32-Pad2)") (class "Default")
      (node (ref "C32") (pin "2") (pinfunction "2_2") (pintype "passive"))
      (node (ref "L4") (pin "2") (pintype "passive"))
      (node (ref "U14") (pin "17") (pinfunction "VBUS_17") (pintype "power_in"))
      (node (ref "U14") (pin "18") (pinfunction "VBUS_18") (pintype "power_in"))
    )
    (net (code "40") (name "Net-(LED1-Pad2)") (class "Default")
      (node (ref "LED1") (pin "2") (pinfunction "2_2") (pintype "passive"))
      (node (ref "R153") (pin "1") (pinfunction "1_1") (pintype "passive"))
    )
    (net (code "41") (name "Net-(LED4-Pad2)") (class "Default")
      (node (ref "LED4") (pin "2") (pinfunction "2_2") (pintype "passive"))
      (node (ref "R53") (pin "1") (pinfunction "1_1") (pintype "passive"))
    )
    (net (code "42") (name "Net-(Q8-D)") (class "Default")
      (node (ref "Q8") (pin "3") (pinfunction "D_3") (pintype "passive"))
      (node (ref "R153") (pin "2") (pinfunction "2_2") (pintype "passive"))
    )
    (net (code "43") (name "Net-(Q9-D)") (class "Default")
      (node (ref "Q9") (pin "3") (pinfunction "D_3") (pintype "passive"))
      (node (ref "R53") (pin "2") (pinfunction "2_2") (pintype "passive"))
    )
    (net (code "44") (name "Net-(U11-~{HOLD}{slash}IO3)") (class "Default")
      (node (ref "R43") (pin "2") (pinfunction "2_2") (pintype "passive"))
      (node (ref "U11") (pin "7") (pinfunction "~{HOLD}/IO3_7") (pintype "bidirectional"))
    )
    (net (code "45") (name "Net-(U11-~{WP}{slash}IO2)") (class "Default")
      (node (ref "R42") (pin "2") (pinfunction "2_2") (pintype "passive"))
      (node (ref "U11") (pin "3") (pinfunction "~{WP}/IO2_3") (pintype "bidirectional"))
    )
    (net (code "46") (name "Net-(U14A-DEBUG_CTL1)") (class "Default")
      (node (ref "R149") (pin "2") (pinfunction "2_2") (pintype "passive"))
      (node (ref "U14") (pin "45") (pinfunction "DEBUG_CTL1_45") (pintype "bidirectional"))
    )
    (net (code "47") (name "Net-(U14A-DEBUG_CTL2)") (class "Default")
      (node (ref "R156") (pin "2") (pinfunction "2_2") (pintype "passive"))
      (node (ref "U14") (pin "44") (pinfunction "DEBUG_CTL2_44") (pintype "bidirectional"))
    )
    (net (code "48") (name "Net-(U14A-GPIO7)") (class "Default")
      (node (ref "R136") (pin "2") (pinfunction "2_2") (pintype "passive"))
      (node (ref "U14") (pin "38") (pinfunction "GPIO7_38") (pintype "bidirectional"))
    )
    (net (code "49") (name "Net-(U14A-RPD_G1)") (class "Default")
      (node (ref "R116") (pin "1") (pinfunction "1_1") (pintype "passive"))
      (node (ref "U14") (pin "12") (pinfunction "RPD_G1_12") (pintype "bidirectional"))
    )
    (net (code "50") (name "Net-(U14A-RPD_G2)") (class "Default")
      (node (ref "R120") (pin "1") (pinfunction "1_1") (pintype "passive"))
      (node (ref "U14") (pin "16") (pinfunction "RPD_G2_16") (pintype "bidirectional"))
    )
    (net (code "51") (name "Net-(U14A-R_OSC)") (class "Default")
      (node (ref "R45") (pin "2") (pinfunction "2_2") (pintype "passive"))
      (node (ref "U14") (pin "52") (pinfunction "R_OSC_52") (pintype "bidirectional"))
    )
    (net (code "52") (name "Net-(U14A-SS)") (class "Default")
      (node (ref "C30") (pin "2") (pinfunction "2_2") (pintype "passive"))
      (node (ref "U14") (pin "3") (pinfunction "SS_3") (pintype "input"))
    )
    (net (code "53") (name "Net-(U14A-SWD_CLK)") (class "Default")
      (node (ref "R148") (pin "2") (pinfunction "2_2") (pintype "passive"))
      (node (ref "U14") (pin "50") (pinfunction "SWD_CLK_50") (pintype "input"))
    )
    (net (code "54") (name "Net-(U14A-SWD_DAT)") (class "Default")
      (node (ref "R147") (pin "2") (pinfunction "2_2") (pintype "passive"))
      (node (ref "U14") (pin "49") (pinfunction "SWD_DAT_49") (pintype "bidirectional"))
    )
    (net (code "55") (name "Net-(U14B-BUSPOWER)") (class "Default")
      (node (ref "R155") (pin "1") (pinfunction "1_1") (pintype "passive"))
      (node (ref "R164") (pin "1") (pinfunction "1_1") (pintype "passive"))
      (node (ref "U14") (pin "22") (pinfunction "BUSPOWER_22") (pintype "power_in"))
    )
    (net (code "56") (name "Net-(U14B-LDO_1V8A)") (class "Default")
      (node (ref "C75") (pin "2") (pinfunction "2_2") (pintype "passive"))
      (node (ref "U14") (pin "56") (pinfunction "LDO_1V8A_56") (pintype "power_in"))
    )
    (net (code "57") (name "Net-(U14B-LDO_1V8D)") (class "Default")
      (node (ref "C74") (pin "2") (pinfunction "2_2") (pintype "passive"))
      (node (ref "U14") (pin "40") (pinfunction "LDO_1V8D_40") (pintype "power_in"))
    )
    (net (code "58") (name "Net-(U14B-LDO_BMC)") (class "Default")
      (node (ref "C100") (pin "2") (pinfunction "2_2") (pintype "passive"))
      (node (ref "U14") (pin "48") (pinfunction "LDO_BMC_48") (pintype "power_in"))
    )
    (net (code "59") (name "USB_3V3") (class "Default")
      (node (ref "C101") (pin "2") (pinfunction "2_2") (pintype "passive"))
      (node (ref "C96") (pin "2") (pinfunction "2_2") (pintype "passive"))
      (node (ref "J4") (pin "2") (pinfunction "2_2") (pintype "passive"))
      (node (ref "J7") (pin "2") (pinfunction "2_2") (pintype "passive"))
      (node (ref "LED1") (pin "1") (pinfunction "1_1") (pintype "passive"))
      (node (ref "LED4") (pin "1") (pinfunction "1_1") (pintype "passive"))
      (node (ref "R138") (pin "1") (pinfunction "1_1") (pintype "passive"))
      (node (ref "R139") (pin "1") (pinfunction "1_1") (pintype "passive"))
      (node (ref "R147") (pin "1") (pinfunction "1_1") (pintype "passive"))
      (node (ref "R150") (pin "1") (pinfunction "1_1") (pintype "passive"))
      (node (ref "R155") (pin "2") (pinfunction "2_2") (pintype "passive"))
      (node (ref "R157") (pin "1") (pinfunction "1_1") (pintype "passive"))
      (node (ref "R158") (pin "1") (pinfunction "1_1") (pintype "passive"))
      (node (ref "R42") (pin "1") (pinfunction "1_1") (pintype "passive"))
      (node (ref "R43") (pin "1") (pinfunction "1_1") (pintype "passive"))
      (node (ref "R54") (pin "2") (pinfunction "2_2") (pintype "passive"))
      (node (ref "R58") (pin "1") (pinfunction "1_1") (pintype "passive"))
      (node (ref "R59") (pin "1") (pinfunction "1_1") (pintype "passive"))
      (node (ref "U11") (pin "8") (pinfunction "VCC_8") (pintype "power_in"))
      (node (ref "U14") (pin "42") (pinfunction "VDDIO_42") (pintype "power_in"))
      (node (ref "U14") (pin "51") (pinfunction "LDO_3V3_51") (pintype "power_in"))
    )
    (net (code "60") (name "VBUS") (class "Default") (node (ref "L4") (pin "1") (pintype "passive")))
    (net (code "61") (name "V_USB_HV") (class "Default")
      (node (ref "C88") (pin "2") (pinfunction "2_2") (pintype "passive"))
      (node (ref "C89") (pin "2") (pinfunction "2_2") (pintype "passive"))
      (node (ref "U14") (pin "33") (pinfunction "PP_HV_33") (pintype "power_in"))
      (node (ref "U14") (pin "34") (pinfunction "PP_HV_34") (pintype "power_in"))
    )
    (net (code "62") (name "unconnected-(U14A-GPIO2-Pad25)") (class "Default")
      (node (ref "U14") (pin "25") (pinfunction "GPIO2_25") (pintype "bidirectional+no_connect"))
    )
    (net (code "63") (name "unconnected-(U14A-GPIO8-Pad1)") (class "Default")
      (node (ref "U14") (pin "1") (pinfunction "GPIO8_1") (pintype "bidirectional+no_connect"))
    )
    (net (code "64") (name "unconnected-(U14A-HV_GATE1-Pad31)") (class "Default")
      (node (ref "U14") (pin "31") (pinfunction "HV_GATE1_31") (pintype "output"))
    )
    (net (code "65") (name "unconnected-(U14A-HV_GATE2-Pad32)") (class "Default")
      (node (ref "U14") (pin "32") (pinfunction "HV_GATE2_32") (pintype "output"))
    )
    (net (code "66") (name "unconnected-(U14A-SENSEN-Pad29)") (class "Default")
      (node (ref "U14") (pin "29") (pinfunction "SENSEN_29") (pintype "input"))
    )
    (net (code "67") (name "unconnected-(U14A-SENSEP-Pad30)") (class "Default")
      (node (ref "U14") (pin "30") (pinfunction "SENSEP_30") (pintype "input"))
    )
  )
)
